# RadioMusic_B.net
KiCad netlist of a schematic drawn in EAGLE
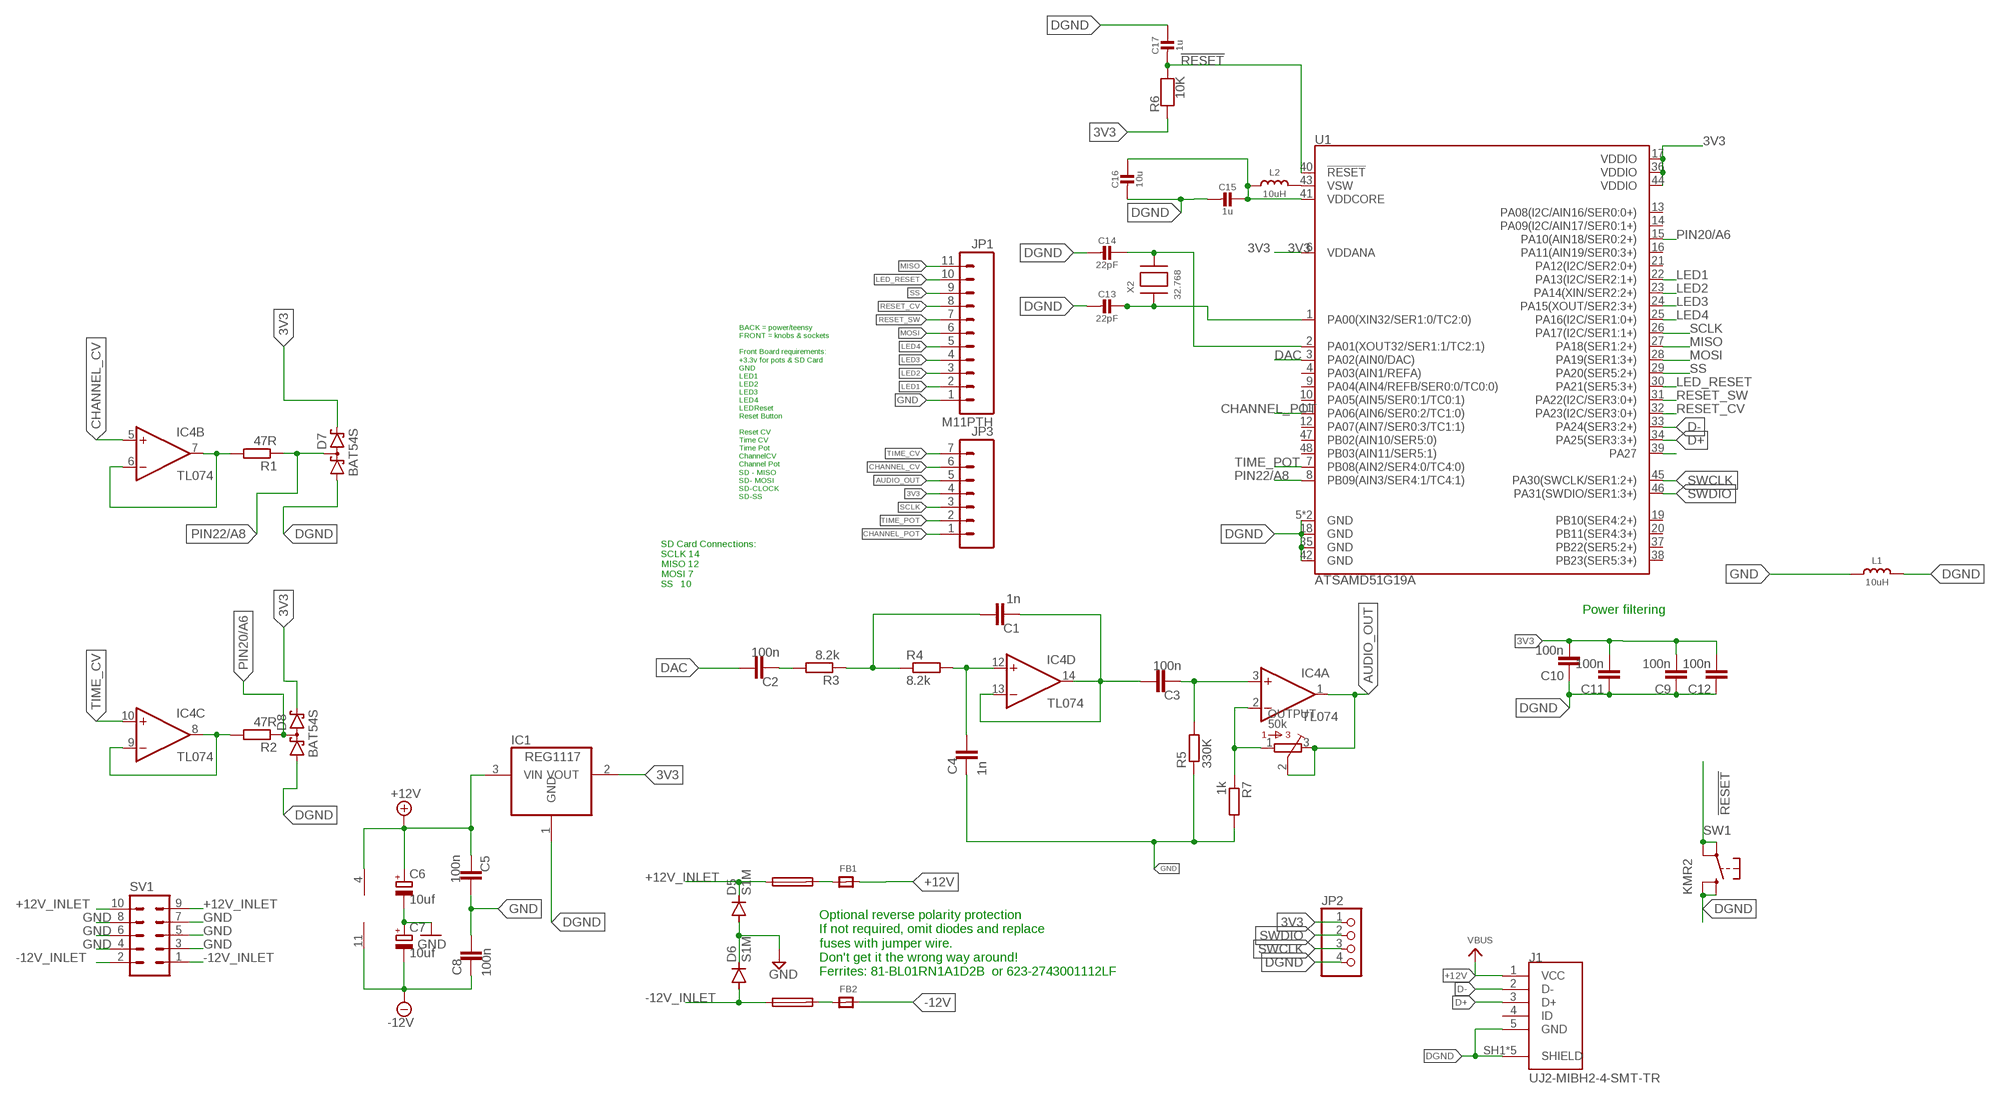
[diagram p0: schematic, sheet 1]

(export (version "E")
  (design (tool "Eeschema 10.0.6"))
  (components
    (comp (ref "C1")
      (value "1n")
      (footprint "eagle-import:C0603")
      (libsource (lib "eagle-import") (part "C-EUC0603"))
    )
    (comp (ref "C2")
      (value "100n")
      (footprint "eagle-import:C0603")
      (libsource (lib "eagle-import") (part "C-EUC0603"))
    )
    (comp (ref "C3")
      (value "100n")
      (footprint "eagle-import:C0603")
      (libsource (lib "eagle-import") (part "C-EUC0603"))
    )
    (comp (ref "C4")
      (value "1n")
      (footprint "eagle-import:C0603")
      (libsource (lib "eagle-import") (part "C-EUC0603"))
    )
    (comp (ref "C5")
      (value "100n")
      (footprint "eagle-import:C0603")
      (libsource (lib "eagle-import") (part "C-EUC0603"))
    )
    (comp (ref "C6")
      (value "10uf")
      (footprint "eagle-import:PANASONIC_B")
      (libsource (lib "eagle-import") (part "CPOL-EUB"))
    )
    (comp (ref "C7")
      (value "10uf")
      (footprint "eagle-import:PANASONIC_B")
      (libsource (lib "eagle-import") (part "CPOL-EUB"))
    )
    (comp (ref "C8")
      (value "100n")
      (footprint "eagle-import:C0603")
      (libsource (lib "eagle-import") (part "C-EUC0603"))
    )
    (comp (ref "C9")
      (value "100n")
      (footprint "eagle-import:C0603")
      (libsource (lib "eagle-import") (part "C-EUC0603"))
    )
    (comp (ref "C10")
      (value "100n")
      (footprint "eagle-import:C0603")
      (libsource (lib "eagle-import") (part "C-EUC0603"))
    )
    (comp (ref "C11")
      (value "100n")
      (footprint "eagle-import:C0603")
      (libsource (lib "eagle-import") (part "C-EUC0603"))
    )
    (comp (ref "C12")
      (value "100n")
      (footprint "eagle-import:C0603")
      (libsource (lib "eagle-import") (part "C-EUC0603"))
    )
    (comp (ref "C13")
      (value "22pF")
      (footprint "eagle-import:0603-NO")
      (libsource (lib "eagle-import") (part "CAP_CERAMIC0603_NO"))
    )
    (comp (ref "C14")
      (value "22pF")
      (footprint "eagle-import:0603-NO")
      (libsource (lib "eagle-import") (part "CAP_CERAMIC0603_NO"))
    )
    (comp (ref "C15")
      (value "1u")
      (footprint "eagle-import:0603-NO")
      (libsource (lib "eagle-import") (part "CAP_CERAMIC0603_NO"))
    )
    (comp (ref "C16")
      (value "10u")
      (footprint "eagle-import:0805-NO")
      (libsource (lib "eagle-import") (part "CAP_CERAMIC0805-NOOUTLINE"))
    )
    (comp (ref "C17")
      (value "1u")
      (footprint "eagle-import:0603-NO")
      (libsource (lib "eagle-import") (part "CAP_CERAMIC0603_NO"))
    )
    (comp (ref "D5")
      (value "S1M")
      (footprint "eagle-import:SMA")
      (libsource (lib "eagle-import") (part "S1M"))
    )
    (comp (ref "D6")
      (value "S1M")
      (footprint "eagle-import:SMA")
      (libsource (lib "eagle-import") (part "S1M"))
    )
    (comp (ref "D7")
      (value "BAT54S")
      (footprint "eagle-import:SOT23")
      (libsource (lib "eagle-import") (part "BAT54S"))
    )
    (comp (ref "D8")
      (value "BAT54S")
      (footprint "eagle-import:SOT23")
      (libsource (lib "eagle-import") (part "BAT54S"))
    )
    (comp (ref "F1")
      (value "FUSE")
      (footprint "eagle-import:F1206")
      (libsource (lib "eagle-import") (part "FUSE"))
    )
    (comp (ref "F2")
      (value "FUSE")
      (footprint "eagle-import:F1206")
      (libsource (lib "eagle-import") (part "FUSE"))
    )
    (comp (ref "FB1")
      (value "FERRITE_0805")
      (footprint "eagle-import:_0805")
      (libsource (lib "eagle-import") (part "FERRITE_0805"))
    )
    (comp (ref "FB2")
      (value "FERRITE_0805")
      (footprint "eagle-import:_0805")
      (libsource (lib "eagle-import") (part "FERRITE_0805"))
    )
    (comp (ref "IC1")
      (value "REG1117")
      (footprint "eagle-import:SOT223")
      (libsource (lib "eagle-import") (part "REG1117"))
    )
    (comp (ref "IC4")
      (value "TL074")
      (footprint "eagle-import:SO14")
      (libsource (lib "eagle-import") (part "TL074_SMD"))
    )
    (comp (ref "J1")
      (value "UJ2-MIBH2-4-SMT-TR")
      (footprint "eagle-import:CUI_UJ2-MIBH2-4-SMT-TR")
      (fields (field (name "MF") "CUI Inc."))
      (libsource (lib "eagle-import") (part "UJ2-MIBH2-4-SMT-TR"))
    )
    (comp (ref "JP1")
      (value "M11PTH")
      (footprint "eagle-import:1X11")
      (libsource (lib "eagle-import") (part "M11PTH"))
    )
    (comp (ref "JP2")
      (value "PINHD-1X4")
      (footprint "eagle-import:1X04")
      (libsource (lib "eagle-import") (part "PINHD-1X4"))
    )
    (comp (ref "JP3")
      (value "M07")
      (footprint "eagle-import:1X07")
      (libsource (lib "eagle-import") (part "M07"))
    )
    (comp (ref "L1")
      (value "10uH")
      (footprint "eagle-import:INDUCTOR_1007")
      (libsource (lib "eagle-import") (part "INDUCTOR"))
    )
    (comp (ref "L2")
      (value "10uH")
      (footprint "eagle-import:INDUCTOR_1007")
      (libsource (lib "eagle-import") (part "INDUCTOR"))
    )
    (comp (ref "OUTPUT")
      (value "50k")
      (footprint "eagle-import:3362P")
      (libsource (lib "eagle-import") (part "3362P"))
    )
    (comp (ref "R1")
      (value "47R")
      (footprint "eagle-import:R0603")
      (libsource (lib "eagle-import") (part "R-EU_R0603"))
    )
    (comp (ref "R2")
      (value "47R")
      (footprint "eagle-import:R0603")
      (libsource (lib "eagle-import") (part "R-EU_R0603"))
    )
    (comp (ref "R3")
      (value "8.2k")
      (footprint "eagle-import:R0603")
      (libsource (lib "eagle-import") (part "R-EU_R0603"))
    )
    (comp (ref "R4")
      (value "8.2k")
      (footprint "eagle-import:R0603")
      (libsource (lib "eagle-import") (part "R-EU_R0603"))
    )
    (comp (ref "R5")
      (value "330K")
      (footprint "eagle-import:R0603")
      (libsource (lib "eagle-import") (part "R-EU_R0603"))
    )
    (comp (ref "R6")
      (value "10K")
      (footprint "eagle-import:0603-NO")
      (libsource (lib "eagle-import") (part "RESISTOR_0603_NOOUT"))
    )
    (comp (ref "R7")
      (value "1k")
      (footprint "eagle-import:R0603")
      (libsource (lib "eagle-import") (part "R-EU_R0603"))
    )
    (comp (ref "SV1")
      (value "10_PIN_HEADER")
      (footprint "eagle-import:MA05-2")
      (libsource (lib "eagle-import") (part "10_PIN_HEADER"))
    )
    (comp (ref "SW1")
      (value "KMR2")
      (footprint "eagle-import:BTN_KMR2_4.6X2.8")
      (libsource (lib "eagle-import") (part "SWITCH_TACT_SMT4.6X2.8"))
    )
    (comp (ref "U1")
      (value "ATSAMD51G19A")
      (footprint "eagle-import:QFN-48")
      (libsource (lib "eagle-import") (part "ATSAMD51G19A"))
    )
    (comp (ref "X2")
      (value "32.768")
      (footprint "eagle-import:XTAL3215")
      (libsource (lib "eagle-import") (part "XTAL-3.2X1.5"))
    )
  )
  (nets
    (net (code "1") (name "+12V") (class "Default")
      (node (ref "C5") (pin "2") (pinfunction "2_2") (pintype "passive"))
      (node (ref "C6") (pin "+") (pinfunction "+_+") (pintype "passive"))
      (node (ref "FB1") (pin "2") (pinfunction "P$2_2") (pintype "passive"))
      (node (ref "IC1") (pin "3") (pinfunction "VIN_3") (pintype "input"))
      (node (ref "IC4") (pin "4") (pinfunction "V+_4") (pintype "power_in"))
      (node (ref "J1") (pin "1") (pinfunction "VCC_1") (pintype "passive"))
    )
    (net (code "2") (name "-12V") (class "Default")
      (node (ref "C7") (pin "-") (pinfunction "-_-") (pintype "passive"))
      (node (ref "C8") (pin "2") (pinfunction "2_2") (pintype "passive"))
      (node (ref "FB2") (pin "2") (pinfunction "P$2_2") (pintype "passive"))
      (node (ref "IC4") (pin "11") (pinfunction "V-_11") (pintype "power_in"))
    )
    (net (code "3") (name "/+12V_INLET") (class "Default")
      (node (ref "D5") (pin "C") (pinfunction "C_C") (pintype "passive"))
      (node (ref "F1") (pin "1") (pinfunction "1_1") (pintype "passive"))
      (node (ref "SV1") (pin "10") (pinfunction "10_10") (pintype "passive"))
      (node (ref "SV1") (pin "9") (pinfunction "9_9") (pintype "passive"))
    )
    (net (code "4") (name "/-12V_INLET") (class "Default")
      (node (ref "D6") (pin "A") (pinfunction "A_A") (pintype "passive"))
      (node (ref "F2") (pin "1") (pinfunction "1_1") (pintype "passive"))
      (node (ref "SV1") (pin "1") (pinfunction "1_1") (pintype "passive"))
      (node (ref "SV1") (pin "2") (pinfunction "2_2") (pintype "passive"))
    )
    (net (code "5") (name "/~{RESET}") (class "Default")
      (node (ref "C17") (pin "2") (pinfunction "2_2") (pintype "passive"))
      (node (ref "R6") (pin "2") (pinfunction "2_2") (pintype "passive"))
      (node (ref "SW1") (pin "A") (pinfunction "P_A") (pintype "passive"))
      (node (ref "SW1") (pin "A'") (pinfunction "P1_A'") (pintype "passive"))
      (node (ref "U1") (pin "40") (pinfunction "~{RESET}_40") (pintype "bidirectional"))
    )
    (net (code "6") (name "3V3") (class "Default")
      (node (ref "C10") (pin "2") (pinfunction "2_2") (pintype "passive"))
      (node (ref "C11") (pin "2") (pinfunction "2_2") (pintype "passive"))
      (node (ref "C12") (pin "2") (pinfunction "2_2") (pintype "passive"))
      (node (ref "C15") (pin "1") (pinfunction "1_1") (pintype "passive"))
      (node (ref "C16") (pin "1") (pinfunction "1_1") (pintype "passive"))
      (node (ref "C9") (pin "2") (pinfunction "2_2") (pintype "passive"))
      (node (ref "D7") (pin "2") (pinfunction "C2_2") (pintype "passive"))
      (node (ref "D8") (pin "2") (pinfunction "C2_2") (pintype "passive"))
      (node (ref "IC1") (pin "2") (pinfunction "VOUT_2") (pintype "output"))
      (node (ref "JP2") (pin "1") (pinfunction "1_1") (pintype "passive"))
      (node (ref "JP3") (pin "4") (pinfunction "4_4") (pintype "passive"))
      (node (ref "L2") (pin "P$1") (pinfunction "1_P$1") (pintype "passive"))
      (node (ref "R6") (pin "1") (pinfunction "1_1") (pintype "passive"))
      (node (ref "U1") (pin "17") (pinfunction "VDDIO_17") (pintype "bidirectional"))
      (node (ref "U1") (pin "36") (pinfunction "VDDIO_36") (pintype "bidirectional"))
      (node (ref "U1") (pin "41") (pinfunction "VDDCORE_41") (pintype "bidirectional"))
      (node (ref "U1") (pin "44") (pinfunction "VDDIO_44") (pintype "bidirectional"))
      (node (ref "U1") (pin "6") (pinfunction "VDDANA_6") (pintype "bidirectional"))
    )
    (net (code "7") (name "AUDIO_OUT") (class "Default")
      (node (ref "IC4") (pin "1") (pinfunction "OUT_1") (pintype "output"))
      (node (ref "JP3") (pin "5") (pinfunction "5_5") (pintype "passive"))
      (node (ref "OUTPUT") (pin "2") (pinfunction "2_2") (pintype "passive"))
      (node (ref "OUTPUT") (pin "3") (pinfunction "3_3") (pintype "passive"))
    )
    (net (code "8") (name "CHANNEL_CV") (class "Default")
      (node (ref "IC4") (pin "5") (pinfunction "+IN_5") (pintype "input"))
      (node (ref "JP3") (pin "6") (pinfunction "6_6") (pintype "passive"))
    )
    (net (code "9") (name "CHANNEL_POT") (class "Default")
      (node (ref "JP3") (pin "1") (pinfunction "1_1") (pintype "passive"))
      (node (ref "U1") (pin "11") (pinfunction "PA06(AIN6/SER0:2/TC1:0)_11") (pintype "bidirectional"))
    )
    (net (code "10") (name "D+") (class "Default")
      (node (ref "J1") (pin "3") (pinfunction "D+_3") (pintype "passive"))
      (node (ref "U1") (pin "34") (pinfunction "PA25(SER3:3+)_34") (pintype "bidirectional"))
    )
    (net (code "11") (name "D-") (class "Default")
      (node (ref "J1") (pin "2") (pinfunction "D-_2") (pintype "passive"))
      (node (ref "U1") (pin "33") (pinfunction "PA24(SER3:2+)_33") (pintype "bidirectional"))
    )
    (net (code "12") (name "DAC") (class "Default")
      (node (ref "C2") (pin "1") (pinfunction "1_1") (pintype "passive"))
      (node (ref "U1") (pin "3") (pinfunction "PA02(AIN0/DAC)_3") (pintype "bidirectional"))
    )
    (net (code "13") (name "DGND") (class "Default")
      (node (ref "C10") (pin "1") (pinfunction "1_1") (pintype "passive"))
      (node (ref "C11") (pin "1") (pinfunction "1_1") (pintype "passive"))
      (node (ref "C12") (pin "1") (pinfunction "1_1") (pintype "passive"))
      (node (ref "C13") (pin "2") (pinfunction "2_2") (pintype "passive"))
      (node (ref "C14") (pin "2") (pinfunction "2_2") (pintype "passive"))
      (node (ref "C15") (pin "2") (pinfunction "2_2") (pintype "passive"))
      (node (ref "C16") (pin "2") (pinfunction "2_2") (pintype "passive"))
      (node (ref "C17") (pin "1") (pinfunction "1_1") (pintype "passive"))
      (node (ref "C9") (pin "1") (pinfunction "1_1") (pintype "passive"))
      (node (ref "D7") (pin "1") (pinfunction "A1_1") (pintype "passive"))
      (node (ref "D8") (pin "1") (pinfunction "A1_1") (pintype "passive"))
      (node (ref "IC1") (pin "1") (pinfunction "GND_1") (pintype "power_in"))
      (node (ref "J1") (pin "5") (pinfunction "GND_5") (pintype "passive"))
      (node (ref "J1") (pin "SH1") (pinfunction "SHIELD_SH1") (pintype "passive"))
      (node (ref "J1") (pin "SH2") (pinfunction "SHIELD_SH2") (pintype "passive"))
      (node (ref "J1") (pin "SH3") (pinfunction "SHIELD_SH3") (pintype "passive"))
      (node (ref "J1") (pin "SH4") (pinfunction "SHIELD_SH4") (pintype "passive"))
      (node (ref "J1") (pin "SH5") (pinfunction "SHIELD_SH5") (pintype "passive"))
      (node (ref "JP2") (pin "4") (pinfunction "4_4") (pintype "passive"))
      (node (ref "L1") (pin "P$2") (pinfunction "2_P$2") (pintype "passive"))
      (node (ref "SW1") (pin "B") (pinfunction "S_B") (pintype "passive"))
      (node (ref "SW1") (pin "B'") (pinfunction "S1_B'") (pintype "passive"))
      (node (ref "U1") (pin "18") (pinfunction "GND_18") (pintype "bidirectional"))
      (node (ref "U1") (pin "35") (pinfunction "GND_35") (pintype "bidirectional"))
      (node (ref "U1") (pin "42") (pinfunction "GND_42") (pintype "bidirectional"))
      (node (ref "U1") (pin "5") (pinfunction "GND_5") (pintype "bidirectional"))
      (node (ref "U1") (pin "EP") (pinfunction "GND_EP") (pintype "bidirectional"))
    )
    (net (code "14") (name "GND") (class "Default")
      (node (ref "C4") (pin "2") (pinfunction "2_2") (pintype "passive"))
      (node (ref "C5") (pin "1") (pinfunction "1_1") (pintype "passive"))
      (node (ref "C6") (pin "-") (pinfunction "-_-") (pintype "passive"))
      (node (ref "C7") (pin "+") (pinfunction "+_+") (pintype "passive"))
      (node (ref "C8") (pin "1") (pinfunction "1_1") (pintype "passive"))
      (node (ref "D5") (pin "A") (pinfunction "A_A") (pintype "passive"))
      (node (ref "D6") (pin "C") (pinfunction "C_C") (pintype "passive"))
      (node (ref "JP1") (pin "1") (pinfunction "1_1") (pintype "passive"))
      (node (ref "L1") (pin "P$1") (pinfunction "1_P$1") (pintype "passive"))
      (node (ref "R5") (pin "1") (pinfunction "1_1") (pintype "passive"))
      (node (ref "R7") (pin "2") (pinfunction "2_2") (pintype "passive"))
      (node (ref "SV1") (pin "3") (pinfunction "3_3") (pintype "passive"))
      (node (ref "SV1") (pin "4") (pinfunction "4_4") (pintype "passive"))
      (node (ref "SV1") (pin "5") (pinfunction "5_5") (pintype "passive"))
      (node (ref "SV1") (pin "6") (pinfunction "6_6") (pintype "passive"))
      (node (ref "SV1") (pin "7") (pinfunction "7_7") (pintype "passive"))
      (node (ref "SV1") (pin "8") (pinfunction "8_8") (pintype "passive"))
    )
    (net (code "15") (name "LED1") (class "Default")
      (node (ref "JP1") (pin "2") (pinfunction "2_2") (pintype "passive"))
      (node (ref "U1") (pin "22") (pinfunction "PA13(I2C/SER2:1+)_22") (pintype "bidirectional"))
    )
    (net (code "16") (name "LED2") (class "Default")
      (node (ref "JP1") (pin "3") (pinfunction "3_3") (pintype "passive"))
      (node (ref "U1") (pin "23") (pinfunction "PA14(XIN/SER2:2+)_23") (pintype "bidirectional"))
    )
    (net (code "17") (name "LED3") (class "Default")
      (node (ref "JP1") (pin "4") (pinfunction "4_4") (pintype "passive"))
      (node (ref "U1") (pin "24") (pinfunction "PA15(XOUT/SER2:3+)_24") (pintype "bidirectional"))
    )
    (net (code "18") (name "LED4") (class "Default")
      (node (ref "JP1") (pin "5") (pinfunction "5_5") (pintype "passive"))
      (node (ref "U1") (pin "25") (pinfunction "PA16(I2C/SER1:0+)_25") (pintype "bidirectional"))
    )
    (net (code "19") (name "LED_RESET") (class "Default")
      (node (ref "JP1") (pin "10") (pinfunction "10_10") (pintype "passive"))
      (node (ref "U1") (pin "30") (pinfunction "PA21(SER5:3+)_30") (pintype "bidirectional"))
    )
    (net (code "20") (name "MISO") (class "Default")
      (node (ref "JP1") (pin "11") (pinfunction "11_11") (pintype "passive"))
      (node (ref "U1") (pin "27") (pinfunction "PA18(SER1:2+)_27") (pintype "bidirectional"))
    )
    (net (code "21") (name "MOSI") (class "Default")
      (node (ref "JP1") (pin "6") (pinfunction "6_6") (pintype "passive"))
      (node (ref "U1") (pin "28") (pinfunction "PA19(SER1:3+)_28") (pintype "bidirectional"))
    )
    (net (code "22") (name "Net-(C1-Pad1)") (class "Default")
      (node (ref "C1") (pin "1") (pinfunction "1_1") (pintype "passive"))
      (node (ref "R3") (pin "1") (pinfunction "1_1") (pintype "passive"))
      (node (ref "R4") (pin "1") (pinfunction "1_1") (pintype "passive"))
    )
    (net (code "23") (name "Net-(C2-Pad2)") (class "Default")
      (node (ref "C2") (pin "2") (pinfunction "2_2") (pintype "passive"))
      (node (ref "R3") (pin "2") (pinfunction "2_2") (pintype "passive"))
    )
    (net (code "24") (name "Net-(FB1-P$1)") (class "Default")
      (node (ref "F1") (pin "2") (pinfunction "2_2") (pintype "passive"))
      (node (ref "FB1") (pin "1") (pinfunction "P$1_1") (pintype "passive"))
    )
    (net (code "25") (name "Net-(FB2-P$1)") (class "Default")
      (node (ref "F2") (pin "2") (pinfunction "2_2") (pintype "passive"))
      (node (ref "FB2") (pin "1") (pinfunction "P$1_1") (pintype "passive"))
    )
    (net (code "26") (name "Net-(IC4A-+IN)") (class "Default")
      (node (ref "C3") (pin "2") (pinfunction "2_2") (pintype "passive"))
      (node (ref "IC4") (pin "3") (pinfunction "+IN_3") (pintype "input"))
      (node (ref "R5") (pin "2") (pinfunction "2_2") (pintype "passive"))
    )
    (net (code "27") (name "Net-(IC4A--IN)") (class "Default")
      (node (ref "IC4") (pin "2") (pinfunction "-IN_2") (pintype "input"))
      (node (ref "OUTPUT") (pin "1") (pinfunction "1_1") (pintype "passive"))
      (node (ref "R7") (pin "1") (pinfunction "1_1") (pintype "passive"))
    )
    (net (code "28") (name "Net-(IC4B--IN)") (class "Default")
      (node (ref "IC4") (pin "6") (pinfunction "-IN_6") (pintype "input"))
      (node (ref "IC4") (pin "7") (pinfunction "OUT_7") (pintype "output"))
      (node (ref "R1") (pin "2") (pinfunction "2_2") (pintype "passive"))
    )
    (net (code "29") (name "Net-(IC4C--IN)") (class "Default")
      (node (ref "IC4") (pin "8") (pinfunction "OUT_8") (pintype "output"))
      (node (ref "IC4") (pin "9") (pinfunction "-IN_9") (pintype "input"))
      (node (ref "R2") (pin "2") (pinfunction "2_2") (pintype "passive"))
    )
    (net (code "30") (name "Net-(IC4D-+IN)") (class "Default")
      (node (ref "C4") (pin "1") (pinfunction "1_1") (pintype "passive"))
      (node (ref "IC4") (pin "12") (pinfunction "+IN_12") (pintype "input"))
      (node (ref "R4") (pin "2") (pinfunction "2_2") (pintype "passive"))
    )
    (net (code "31") (name "Net-(IC4D--IN)") (class "Default")
      (node (ref "C1") (pin "2") (pinfunction "2_2") (pintype "passive"))
      (node (ref "C3") (pin "1") (pinfunction "1_1") (pintype "passive"))
      (node (ref "IC4") (pin "13") (pinfunction "-IN_13") (pintype "input"))
      (node (ref "IC4") (pin "14") (pinfunction "OUT_14") (pintype "output"))
    )
    (net (code "32") (name "Net-(L2-2)") (class "Default")
      (node (ref "L2") (pin "P$2") (pinfunction "2_P$2") (pintype "passive"))
      (node (ref "U1") (pin "43") (pinfunction "VSW_43") (pintype "bidirectional"))
    )
    (net (code "33") (name "Net-(U1-PA00(XIN32{slash}SER1:0{slash}TC2:0))") (class "Default")
      (node (ref "C13") (pin "1") (pinfunction "1_1") (pintype "passive"))
      (node (ref "U1") (pin "1") (pinfunction "PA00(XIN32/SER1:0/TC2:0)_1") (pintype "bidirectional"))
      (node (ref "X2") (pin "P$1") (pinfunction "P$1_P$1") (pintype "bidirectional"))
    )
    (net (code "34") (name "Net-(U1-PA01(XOUT32{slash}SER1:1{slash}TC2:1))") (class "Default")
      (node (ref "C14") (pin "1") (pinfunction "1_1") (pintype "passive"))
      (node (ref "U1") (pin "2") (pinfunction "PA01(XOUT32/SER1:1/TC2:1)_2") (pintype "bidirectional"))
      (node (ref "X2") (pin "P$2") (pinfunction "P$2_P$2") (pintype "bidirectional"))
    )
    (net (code "35") (name "PIN20{slash}A6") (class "Default")
      (node (ref "D8") (pin "3") (pinfunction "C1A2_3") (pintype "passive"))
      (node (ref "R2") (pin "1") (pinfunction "1_1") (pintype "passive"))
      (node (ref "U1") (pin "15") (pinfunction "PA10(AIN18/SER0:2+)_15") (pintype "bidirectional"))
    )
    (net (code "36") (name "PIN22{slash}A8") (class "Default")
      (node (ref "D7") (pin "3") (pinfunction "C1A2_3") (pintype "passive"))
      (node (ref "R1") (pin "1") (pinfunction "1_1") (pintype "passive"))
      (node (ref "U1") (pin "8") (pinfunction "PB09(AIN3/SER4:1/TC4:1)_8") (pintype "bidirectional"))
    )
    (net (code "37") (name "RESET_CV") (class "Default")
      (node (ref "JP1") (pin "8") (pinfunction "8_8") (pintype "passive"))
      (node (ref "U1") (pin "32") (pinfunction "PA23(I2C/SER3:0+)_32") (pintype "bidirectional"))
    )
    (net (code "38") (name "RESET_SW") (class "Default")
      (node (ref "JP1") (pin "7") (pinfunction "7_7") (pintype "passive"))
      (node (ref "U1") (pin "31") (pinfunction "PA22(I2C/SER3:0+)_31") (pintype "bidirectional"))
    )
    (net (code "39") (name "SCLK") (class "Default")
      (node (ref "JP3") (pin "3") (pinfunction "3_3") (pintype "passive"))
      (node (ref "U1") (pin "26") (pinfunction "PA17(I2C/SER1:1+)_26") (pintype "bidirectional"))
    )
    (net (code "40") (name "SS") (class "Default")
      (node (ref "JP1") (pin "9") (pinfunction "9_9") (pintype "passive"))
      (node (ref "U1") (pin "29") (pinfunction "PA20(SER5:2+)_29") (pintype "bidirectional"))
    )
    (net (code "41") (name "SWCLK") (class "Default")
      (node (ref "JP2") (pin "3") (pinfunction "3_3") (pintype "passive"))
      (node (ref "U1") (pin "45") (pinfunction "PA30(SWCLK/SER1:2+)_45") (pintype "bidirectional"))
    )
    (net (code "42") (name "SWDIO") (class "Default")
      (node (ref "JP2") (pin "2") (pinfunction "2_2") (pintype "passive"))
      (node (ref "U1") (pin "46") (pinfunction "PA31(SWDIO/SER1:3+)_46") (pintype "bidirectional"))
    )
    (net (code "43") (name "TIME_CV") (class "Default")
      (node (ref "IC4") (pin "10") (pinfunction "+IN_10") (pintype "input"))
      (node (ref "JP3") (pin "7") (pinfunction "7_7") (pintype "passive"))
    )
    (net (code "44") (name "TIME_POT") (class "Default")
      (node (ref "JP3") (pin "2") (pinfunction "2_2") (pintype "passive"))
      (node (ref "U1") (pin "7") (pinfunction "PB08(AIN2/SER4:0/TC4:0)_7") (pintype "bidirectional"))
    )
    (net (code "45") (name "unconnected-(J1-ID-Pad4)") (class "Default")
      (node (ref "J1") (pin "4") (pinfunction "ID_4") (pintype "passive"))
    )
    (net (code "46") (name "unconnected-(U1-PA03(AIN1{slash}REFA)-Pad4)") (class "Default")
      (node (ref "U1") (pin "4") (pinfunction "PA03(AIN1/REFA)_4") (pintype "bidirectional"))
    )
    (net (code "47") (name "unconnected-(U1-PA04(AIN4{slash}REFB{slash}SER0:0{slash}TC0:0)-Pad9)") (class "Default")
      (node (ref "U1") (pin "9") (pinfunction "PA04(AIN4/REFB/SER0:0/TC0:0)_9") (pintype "bidirectional"))
    )
    (net (code "48") (name "unconnected-(U1-PA05(AIN5{slash}SER0:1{slash}TC0:1)-Pad10)") (class "Default")
      (node (ref "U1") (pin "10") (pinfunction "PA05(AIN5/SER0:1/TC0:1)_10") (pintype "bidirectional"))
    )
    (net (code "49") (name "unconnected-(U1-PA07(AIN7{slash}SER0:3{slash}TC1:1)-Pad12)") (class "Default")
      (node (ref "U1") (pin "12") (pinfunction "PA07(AIN7/SER0:3/TC1:1)_12") (pintype "bidirectional"))
    )
    (net (code "50") (name "unconnected-(U1-PA08(I2C{slash}AIN16{slash}SER0:0+)-Pad13)") (class "Default")
      (node (ref "U1") (pin "13") (pinfunction "PA08(I2C/AIN16/SER0:0+)_13") (pintype "bidirectional"))
    )
    (net (code "51") (name "unconnected-(U1-PA09(I2C{slash}AIN17{slash}SER0:1+)-Pad14)") (class "Default")
      (node (ref "U1") (pin "14") (pinfunction "PA09(I2C/AIN17/SER0:1+)_14") (pintype "bidirectional"))
    )
    (net (code "52") (name "unconnected-(U1-PA11(AIN19{slash}SER0:3+)-Pad16)") (class "Default")
      (node (ref "U1") (pin "16") (pinfunction "PA11(AIN19/SER0:3+)_16") (pintype "bidirectional"))
    )
    (net (code "53") (name "unconnected-(U1-PA12(I2C{slash}SER2:0+)-Pad21)") (class "Default")
      (node (ref "U1") (pin "21") (pinfunction "PA12(I2C/SER2:0+)_21") (pintype "bidirectional"))
    )
    (net (code "54") (name "unconnected-(U1-PA27-Pad39)") (class "Default")
      (node (ref "U1") (pin "39") (pinfunction "PA27_39") (pintype "bidirectional"))
    )
    (net (code "55") (name "unconnected-(U1-PB02(AIN10{slash}SER5:0)-Pad47)") (class "Default")
      (node (ref "U1") (pin "47") (pinfunction "PB02(AIN10/SER5:0)_47") (pintype "bidirectional"))
    )
    (net (code "56") (name "unconnected-(U1-PB03(AIN11{slash}SER5:1)-Pad48)") (class "Default")
      (node (ref "U1") (pin "48") (pinfunction "PB03(AIN11/SER5:1)_48") (pintype "bidirectional"))
    )
    (net (code "57") (name "unconnected-(U1-PB10(SER4:2+)-Pad19)") (class "Default")
      (node (ref "U1") (pin "19") (pinfunction "PB10(SER4:2+)_19") (pintype "bidirectional"))
    )
    (net (code "58") (name "unconnected-(U1-PB11(SER4:3+)-Pad20)") (class "Default")
      (node (ref "U1") (pin "20") (pinfunction "PB11(SER4:3+)_20") (pintype "bidirectional"))
    )
    (net (code "59") (name "unconnected-(U1-PB22(SER5:2+)-Pad37)") (class "Default")
      (node (ref "U1") (pin "37") (pinfunction "PB22(SER5:2+)_37") (pintype "bidirectional"))
    )
    (net (code "60") (name "unconnected-(U1-PB23(SER5:3+)-Pad38)") (class "Default")
      (node (ref "U1") (pin "38") (pinfunction "PB23(SER5:3+)_38") (pintype "bidirectional"))
    )
  )
)
